# PCB-BI8-1x8SC3x.net
KiCad netlist of a schematic drawn in EAGLE
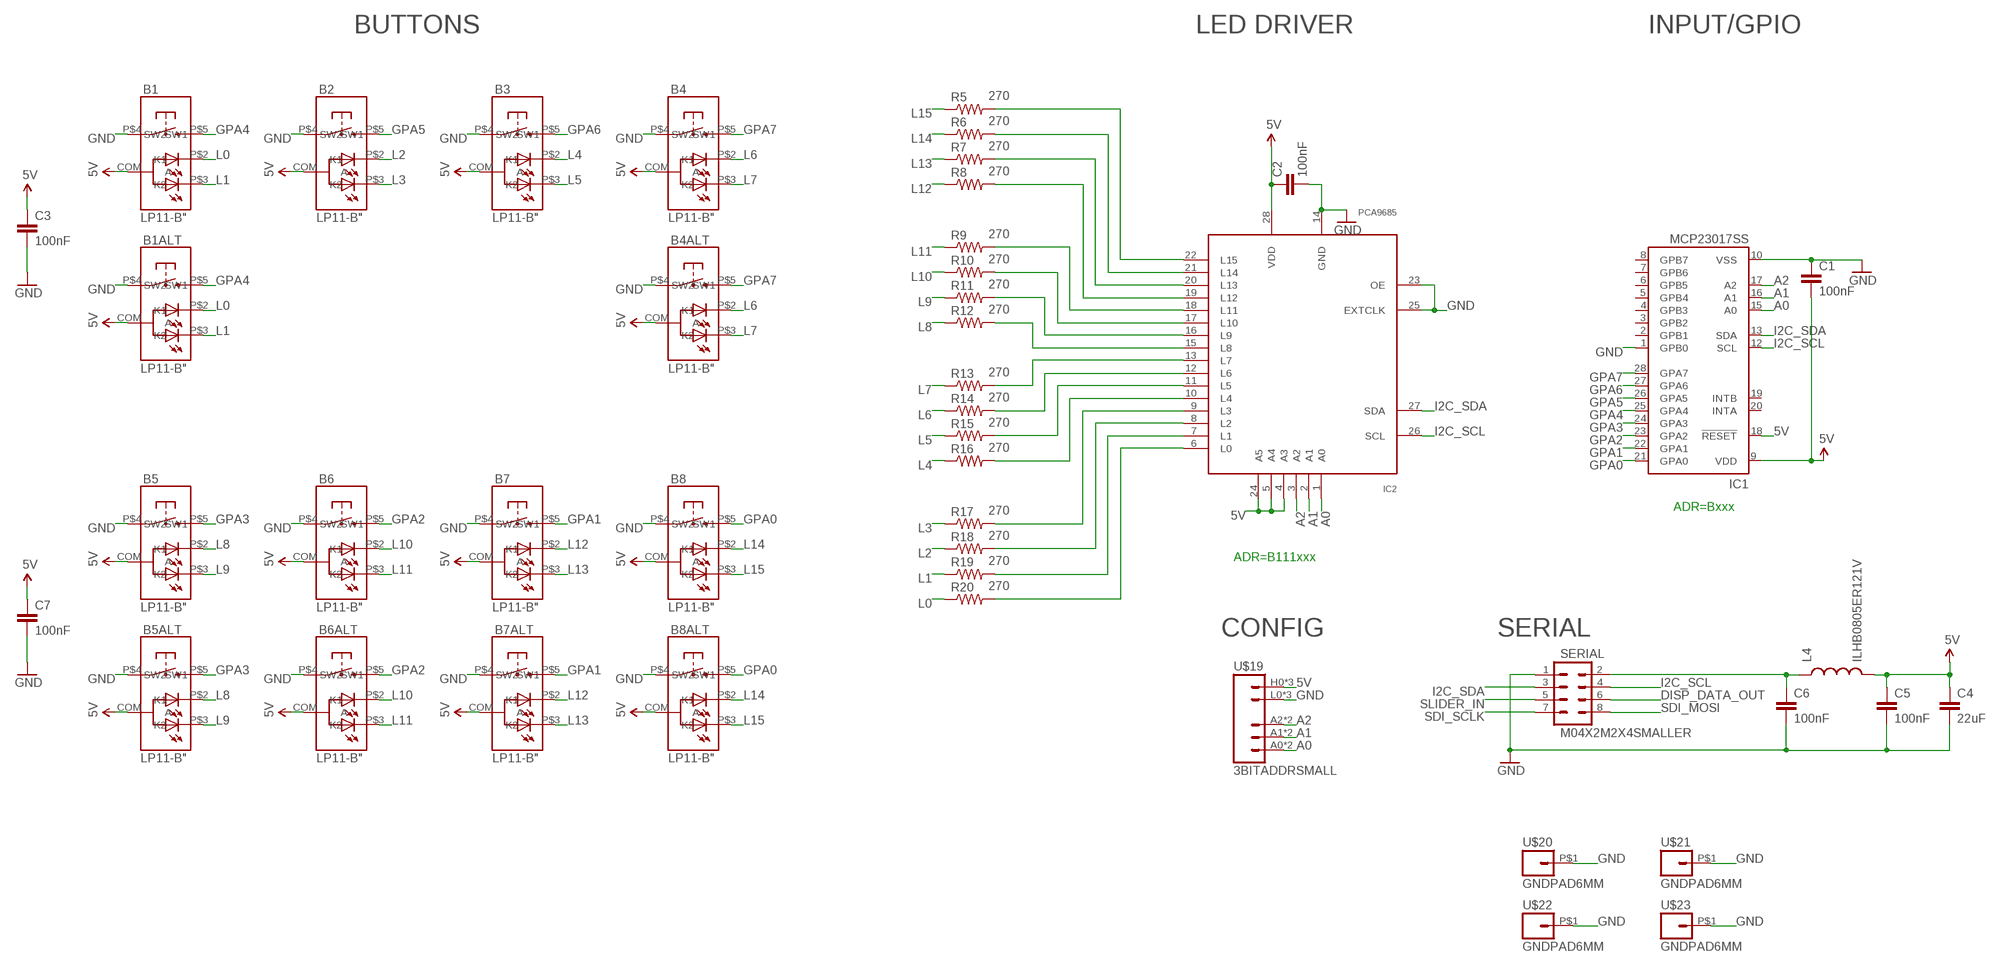
[diagram p0: schematic, sheet 1]

(export (version "E")
  (design (tool "Eeschema 10.0.6"))
  (components
    (comp (ref "B1")
      (value "LP11-B\"")
      (footprint "eagle-import:LP11")
      (libsource (lib "eagle-import") (part "LP11-B{dblquote}"))
    )
    (comp (ref "B1ALT")
      (value "LP11-B\"")
      (footprint "eagle-import:LP11")
      (libsource (lib "eagle-import") (part "LP11-B{dblquote}"))
    )
    (comp (ref "B2")
      (value "LP11-B\"")
      (footprint "eagle-import:LP11")
      (libsource (lib "eagle-import") (part "LP11-B{dblquote}"))
    )
    (comp (ref "B3")
      (value "LP11-B\"")
      (footprint "eagle-import:LP11")
      (libsource (lib "eagle-import") (part "LP11-B{dblquote}"))
    )
    (comp (ref "B4")
      (value "LP11-B\"")
      (footprint "eagle-import:LP11")
      (libsource (lib "eagle-import") (part "LP11-B{dblquote}"))
    )
    (comp (ref "B4ALT")
      (value "LP11-B\"")
      (footprint "eagle-import:LP11")
      (libsource (lib "eagle-import") (part "LP11-B{dblquote}"))
    )
    (comp (ref "B5")
      (value "LP11-B\"")
      (footprint "eagle-import:LP11")
      (libsource (lib "eagle-import") (part "LP11-B{dblquote}"))
    )
    (comp (ref "B5ALT")
      (value "LP11-B\"")
      (footprint "eagle-import:LP11")
      (libsource (lib "eagle-import") (part "LP11-B{dblquote}"))
    )
    (comp (ref "B6")
      (value "LP11-B\"")
      (footprint "eagle-import:LP11")
      (libsource (lib "eagle-import") (part "LP11-B{dblquote}"))
    )
    (comp (ref "B6ALT")
      (value "LP11-B\"")
      (footprint "eagle-import:LP11")
      (libsource (lib "eagle-import") (part "LP11-B{dblquote}"))
    )
    (comp (ref "B7")
      (value "LP11-B\"")
      (footprint "eagle-import:LP11")
      (libsource (lib "eagle-import") (part "LP11-B{dblquote}"))
    )
    (comp (ref "B7ALT")
      (value "LP11-B\"")
      (footprint "eagle-import:LP11")
      (libsource (lib "eagle-import") (part "LP11-B{dblquote}"))
    )
    (comp (ref "B8")
      (value "LP11-B\"")
      (footprint "eagle-import:LP11")
      (libsource (lib "eagle-import") (part "LP11-B{dblquote}"))
    )
    (comp (ref "B8ALT")
      (value "LP11-B\"")
      (footprint "eagle-import:LP11")
      (libsource (lib "eagle-import") (part "LP11-B{dblquote}"))
    )
    (comp (ref "C1")
      (value "100nF")
      (footprint "eagle-import:0603-CAP")
      (libsource (lib "eagle-import") (part "CAP0603-CAP"))
    )
    (comp (ref "C2")
      (value "100nF")
      (footprint "eagle-import:0603-CAP")
      (libsource (lib "eagle-import") (part "CAP0603-CAP"))
    )
    (comp (ref "C3")
      (value "100nF")
      (footprint "eagle-import:0603-CAP")
      (libsource (lib "eagle-import") (part "CAP0603-CAP"))
    )
    (comp (ref "C4")
      (value "22uF")
      (footprint "eagle-import:0805")
      (libsource (lib "eagle-import") (part "CAP0805"))
    )
    (comp (ref "C5")
      (value "100nF")
      (footprint "eagle-import:0603-CAP")
      (libsource (lib "eagle-import") (part "CAP0603-CAP"))
    )
    (comp (ref "C6")
      (value "100nF")
      (footprint "eagle-import:0603-CAP")
      (libsource (lib "eagle-import") (part "CAP0603-CAP"))
    )
    (comp (ref "C7")
      (value "100nF")
      (footprint "eagle-import:0603-CAP")
      (libsource (lib "eagle-import") (part "CAP0603-CAP"))
    )
    (comp (ref "IC1")
      (value "MCP23017SS")
      (footprint "eagle-import:SSOP28")
      (fields
        (field (name "MF") "MICROCHIP")
        (field (name "MPN") "MCP23017-E/SS")
        (field (name "MPN_1") "MCP23017-E/SS")
        (field (name "OC_FARNELL") "1467674")
        (field (name "OC_NEWARK") "31K2960")
      )
      (libsource (lib "eagle-import") (part "MCP23017SS"))
    )
    (comp (ref "IC2")
      (value "PCA9685")
      (footprint "eagle-import:TSSOP28")
      (libsource (lib "eagle-import") (part "PCA9685"))
    )
    (comp (ref "L4")
      (value "ILHB0805ER121V")
      (footprint "eagle-import:0805")
      (libsource (lib "eagle-import") (part "INDUCTOR0805"))
    )
    (comp (ref "R5")
      (value "270")
      (footprint "eagle-import:0603-RES")
      (libsource (lib "eagle-import") (part "RESISTOR0603-RES"))
    )
    (comp (ref "R6")
      (value "270")
      (footprint "eagle-import:0603-RES")
      (libsource (lib "eagle-import") (part "RESISTOR0603-RES"))
    )
    (comp (ref "R7")
      (value "270")
      (footprint "eagle-import:0603-RES")
      (libsource (lib "eagle-import") (part "RESISTOR0603-RES"))
    )
    (comp (ref "R8")
      (value "270")
      (footprint "eagle-import:0603-RES")
      (libsource (lib "eagle-import") (part "RESISTOR0603-RES"))
    )
    (comp (ref "R9")
      (value "270")
      (footprint "eagle-import:0603-RES")
      (libsource (lib "eagle-import") (part "RESISTOR0603-RES"))
    )
    (comp (ref "R10")
      (value "270")
      (footprint "eagle-import:0603-RES")
      (libsource (lib "eagle-import") (part "RESISTOR0603-RES"))
    )
    (comp (ref "R11")
      (value "270")
      (footprint "eagle-import:0603-RES")
      (libsource (lib "eagle-import") (part "RESISTOR0603-RES"))
    )
    (comp (ref "R12")
      (value "270")
      (footprint "eagle-import:0603-RES")
      (libsource (lib "eagle-import") (part "RESISTOR0603-RES"))
    )
    (comp (ref "R13")
      (value "270")
      (footprint "eagle-import:0603-RES")
      (libsource (lib "eagle-import") (part "RESISTOR0603-RES"))
    )
    (comp (ref "R14")
      (value "270")
      (footprint "eagle-import:0603-RES")
      (libsource (lib "eagle-import") (part "RESISTOR0603-RES"))
    )
    (comp (ref "R15")
      (value "270")
      (footprint "eagle-import:0603-RES")
      (libsource (lib "eagle-import") (part "RESISTOR0603-RES"))
    )
    (comp (ref "R16")
      (value "270")
      (footprint "eagle-import:0603-RES")
      (libsource (lib "eagle-import") (part "RESISTOR0603-RES"))
    )
    (comp (ref "R17")
      (value "270")
      (footprint "eagle-import:0603-RES")
      (libsource (lib "eagle-import") (part "RESISTOR0603-RES"))
    )
    (comp (ref "R18")
      (value "270")
      (footprint "eagle-import:0603-RES")
      (libsource (lib "eagle-import") (part "RESISTOR0603-RES"))
    )
    (comp (ref "R19")
      (value "270")
      (footprint "eagle-import:0603-RES")
      (libsource (lib "eagle-import") (part "RESISTOR0603-RES"))
    )
    (comp (ref "R20")
      (value "270")
      (footprint "eagle-import:0603-RES")
      (libsource (lib "eagle-import") (part "RESISTOR0603-RES"))
    )
    (comp (ref "SERIAL")
      (value "M04X2M2X4SMALLER")
      (footprint "eagle-import:M2X4SMALLER")
      (libsource (lib "eagle-import") (part "M04X2M2X4SMALLER"))
    )
    (comp (ref "U$19")
      (value "3BITADDRSMALL")
      (footprint "eagle-import:3BITADDR_SMALL")
      (libsource (lib "eagle-import") (part "3BITADDRSMALL"))
    )
    (comp (ref "U$20")
      (value "GNDPAD6MM")
      (footprint "eagle-import:3.2MMPAD6MM")
      (libsource (lib "eagle-import") (part "GNDPAD6MM"))
    )
    (comp (ref "U$21")
      (value "GNDPAD6MM")
      (footprint "eagle-import:3.2MMPAD6MM")
      (libsource (lib "eagle-import") (part "GNDPAD6MM"))
    )
    (comp (ref "U$22")
      (value "GNDPAD6MM")
      (footprint "eagle-import:3.2MMPAD6MM")
      (libsource (lib "eagle-import") (part "GNDPAD6MM"))
    )
    (comp (ref "U$23")
      (value "GNDPAD6MM")
      (footprint "eagle-import:3.2MMPAD6MM")
      (libsource (lib "eagle-import") (part "GNDPAD6MM"))
    )
  )
  (nets
    (net (code "1") (name "/A0") (class "Default")
      (node (ref "IC1") (pin "15") (pinfunction "A0_15") (pintype "input"))
      (node (ref "IC2") (pin "1") (pinfunction "A0_1") (pintype "input"))
      (node (ref "U$19") (pin "A0") (pinfunction "A0_A0") (pintype "passive"))
      (node (ref "U$19") (pin "AS0") (pinfunction "A0_AS0") (pintype "passive"))
    )
    (net (code "2") (name "/A1") (class "Default")
      (node (ref "IC1") (pin "16") (pinfunction "A1_16") (pintype "input"))
      (node (ref "IC2") (pin "2") (pinfunction "A1_2") (pintype "input"))
      (node (ref "U$19") (pin "A1") (pinfunction "A1_A1") (pintype "passive"))
      (node (ref "U$19") (pin "AS1") (pinfunction "A1_AS1") (pintype "passive"))
    )
    (net (code "3") (name "/A2") (class "Default")
      (node (ref "IC1") (pin "17") (pinfunction "A2_17") (pintype "input"))
      (node (ref "IC2") (pin "3") (pinfunction "A2_3") (pintype "input"))
      (node (ref "U$19") (pin "A2") (pinfunction "A2_A2") (pintype "passive"))
      (node (ref "U$19") (pin "AS2") (pinfunction "A2_AS2") (pintype "passive"))
    )
    (net (code "4") (name "/DISP_DATA_OUT") (class "Default")
      (node (ref "SERIAL") (pin "6") (pinfunction "6_6") (pintype "passive"))
    )
    (net (code "5") (name "/GPA0") (class "Default")
      (node (ref "B8") (pin "P$5") (pinfunction "SW2_P$5") (pintype "bidirectional"))
      (node (ref "B8ALT") (pin "P$5") (pinfunction "SW2_P$5") (pintype "bidirectional"))
      (node (ref "IC1") (pin "21") (pinfunction "GPA0_21") (pintype "bidirectional"))
    )
    (net (code "6") (name "/GPA1") (class "Default")
      (node (ref "B7") (pin "P$5") (pinfunction "SW2_P$5") (pintype "bidirectional"))
      (node (ref "B7ALT") (pin "P$5") (pinfunction "SW2_P$5") (pintype "bidirectional"))
      (node (ref "IC1") (pin "22") (pinfunction "GPA1_22") (pintype "bidirectional"))
    )
    (net (code "7") (name "/GPA2") (class "Default")
      (node (ref "B6") (pin "P$5") (pinfunction "SW2_P$5") (pintype "bidirectional"))
      (node (ref "B6ALT") (pin "P$5") (pinfunction "SW2_P$5") (pintype "bidirectional"))
      (node (ref "IC1") (pin "23") (pinfunction "GPA2_23") (pintype "bidirectional"))
    )
    (net (code "8") (name "/GPA3") (class "Default")
      (node (ref "B5") (pin "P$5") (pinfunction "SW2_P$5") (pintype "bidirectional"))
      (node (ref "B5ALT") (pin "P$5") (pinfunction "SW2_P$5") (pintype "bidirectional"))
      (node (ref "IC1") (pin "24") (pinfunction "GPA3_24") (pintype "bidirectional"))
    )
    (net (code "9") (name "/GPA4") (class "Default")
      (node (ref "B1") (pin "P$5") (pinfunction "SW2_P$5") (pintype "bidirectional"))
      (node (ref "B1ALT") (pin "P$5") (pinfunction "SW2_P$5") (pintype "bidirectional"))
      (node (ref "IC1") (pin "25") (pinfunction "GPA4_25") (pintype "bidirectional"))
    )
    (net (code "10") (name "/GPA5") (class "Default")
      (node (ref "B2") (pin "P$5") (pinfunction "SW2_P$5") (pintype "bidirectional"))
      (node (ref "IC1") (pin "26") (pinfunction "GPA5_26") (pintype "bidirectional"))
    )
    (net (code "11") (name "/GPA6") (class "Default")
      (node (ref "B3") (pin "P$5") (pinfunction "SW2_P$5") (pintype "bidirectional"))
      (node (ref "IC1") (pin "27") (pinfunction "GPA6_27") (pintype "bidirectional"))
    )
    (net (code "12") (name "/GPA7") (class "Default")
      (node (ref "B4") (pin "P$5") (pinfunction "SW2_P$5") (pintype "bidirectional"))
      (node (ref "B4ALT") (pin "P$5") (pinfunction "SW2_P$5") (pintype "bidirectional"))
      (node (ref "IC1") (pin "28") (pinfunction "GPA7_28") (pintype "bidirectional"))
    )
    (net (code "13") (name "/I2C_SCL") (class "Default")
      (node (ref "IC1") (pin "12") (pinfunction "SCL_12") (pintype "input"))
      (node (ref "IC2") (pin "26") (pinfunction "SCL_26") (pintype "input"))
      (node (ref "SERIAL") (pin "4") (pinfunction "4_4") (pintype "passive"))
    )
    (net (code "14") (name "/I2C_SDA") (class "Default")
      (node (ref "IC1") (pin "13") (pinfunction "SDA_13") (pintype "bidirectional"))
      (node (ref "IC2") (pin "27") (pinfunction "SDA_27") (pintype "input"))
      (node (ref "SERIAL") (pin "3") (pinfunction "3_3") (pintype "passive"))
    )
    (net (code "15") (name "/L0") (class "Default")
      (node (ref "B1") (pin "P$2") (pinfunction "K1_P$2") (pintype "bidirectional"))
      (node (ref "B1ALT") (pin "P$2") (pinfunction "K1_P$2") (pintype "bidirectional"))
      (node (ref "R20") (pin "1") (pinfunction "1_1") (pintype "passive"))
    )
    (net (code "16") (name "/L1") (class "Default")
      (node (ref "B1") (pin "P$3") (pinfunction "K2_P$3") (pintype "bidirectional"))
      (node (ref "B1ALT") (pin "P$3") (pinfunction "K2_P$3") (pintype "bidirectional"))
      (node (ref "R19") (pin "1") (pinfunction "1_1") (pintype "passive"))
    )
    (net (code "17") (name "/L2") (class "Default")
      (node (ref "B2") (pin "P$2") (pinfunction "K1_P$2") (pintype "bidirectional"))
      (node (ref "R18") (pin "1") (pinfunction "1_1") (pintype "passive"))
    )
    (net (code "18") (name "/L3") (class "Default")
      (node (ref "B2") (pin "P$3") (pinfunction "K2_P$3") (pintype "bidirectional"))
      (node (ref "R17") (pin "1") (pinfunction "1_1") (pintype "passive"))
    )
    (net (code "19") (name "/L4") (class "Default")
      (node (ref "B3") (pin "P$2") (pinfunction "K1_P$2") (pintype "bidirectional"))
      (node (ref "R16") (pin "1") (pinfunction "1_1") (pintype "passive"))
    )
    (net (code "20") (name "/L5") (class "Default")
      (node (ref "B3") (pin "P$3") (pinfunction "K2_P$3") (pintype "bidirectional"))
      (node (ref "R15") (pin "1") (pinfunction "1_1") (pintype "passive"))
    )
    (net (code "21") (name "/L6") (class "Default")
      (node (ref "B4") (pin "P$2") (pinfunction "K1_P$2") (pintype "bidirectional"))
      (node (ref "B4ALT") (pin "P$2") (pinfunction "K1_P$2") (pintype "bidirectional"))
      (node (ref "R14") (pin "1") (pinfunction "1_1") (pintype "passive"))
    )
    (net (code "22") (name "/L7") (class "Default")
      (node (ref "B4") (pin "P$3") (pinfunction "K2_P$3") (pintype "bidirectional"))
      (node (ref "B4ALT") (pin "P$3") (pinfunction "K2_P$3") (pintype "bidirectional"))
      (node (ref "R13") (pin "1") (pinfunction "1_1") (pintype "passive"))
    )
    (net (code "23") (name "/L8") (class "Default")
      (node (ref "B5") (pin "P$2") (pinfunction "K1_P$2") (pintype "bidirectional"))
      (node (ref "B5ALT") (pin "P$2") (pinfunction "K1_P$2") (pintype "bidirectional"))
      (node (ref "R12") (pin "1") (pinfunction "1_1") (pintype "passive"))
    )
    (net (code "24") (name "/L9") (class "Default")
      (node (ref "B5") (pin "P$3") (pinfunction "K2_P$3") (pintype "bidirectional"))
      (node (ref "B5ALT") (pin "P$3") (pinfunction "K2_P$3") (pintype "bidirectional"))
      (node (ref "R11") (pin "1") (pinfunction "1_1") (pintype "passive"))
    )
    (net (code "25") (name "/L10") (class "Default")
      (node (ref "B6") (pin "P$2") (pinfunction "K1_P$2") (pintype "bidirectional"))
      (node (ref "B6ALT") (pin "P$2") (pinfunction "K1_P$2") (pintype "bidirectional"))
      (node (ref "R10") (pin "1") (pinfunction "1_1") (pintype "passive"))
    )
    (net (code "26") (name "/L11") (class "Default")
      (node (ref "B6") (pin "P$3") (pinfunction "K2_P$3") (pintype "bidirectional"))
      (node (ref "B6ALT") (pin "P$3") (pinfunction "K2_P$3") (pintype "bidirectional"))
      (node (ref "R9") (pin "1") (pinfunction "1_1") (pintype "passive"))
    )
    (net (code "27") (name "/L12") (class "Default")
      (node (ref "B7") (pin "P$2") (pinfunction "K1_P$2") (pintype "bidirectional"))
      (node (ref "B7ALT") (pin "P$2") (pinfunction "K1_P$2") (pintype "bidirectional"))
      (node (ref "R8") (pin "1") (pinfunction "1_1") (pintype "passive"))
    )
    (net (code "28") (name "/L13") (class "Default")
      (node (ref "B7") (pin "P$3") (pinfunction "K2_P$3") (pintype "bidirectional"))
      (node (ref "B7ALT") (pin "P$3") (pinfunction "K2_P$3") (pintype "bidirectional"))
      (node (ref "R7") (pin "1") (pinfunction "1_1") (pintype "passive"))
    )
    (net (code "29") (name "/L14") (class "Default")
      (node (ref "B8") (pin "P$2") (pinfunction "K1_P$2") (pintype "bidirectional"))
      (node (ref "B8ALT") (pin "P$2") (pinfunction "K1_P$2") (pintype "bidirectional"))
      (node (ref "R6") (pin "1") (pinfunction "1_1") (pintype "passive"))
    )
    (net (code "30") (name "/L15") (class "Default")
      (node (ref "B8") (pin "P$3") (pinfunction "K2_P$3") (pintype "bidirectional"))
      (node (ref "B8ALT") (pin "P$3") (pinfunction "K2_P$3") (pintype "bidirectional"))
      (node (ref "R5") (pin "1") (pinfunction "1_1") (pintype "passive"))
    )
    (net (code "31") (name "/SDI_MOSI") (class "Default")
      (node (ref "SERIAL") (pin "8") (pinfunction "8_8") (pintype "passive"))
    )
    (net (code "32") (name "/SDI_SCLK") (class "Default")
      (node (ref "SERIAL") (pin "7") (pinfunction "7_7") (pintype "passive"))
    )
    (net (code "33") (name "/SLIDER_IN") (class "Default")
      (node (ref "SERIAL") (pin "5") (pinfunction "5_5") (pintype "passive"))
    )
    (net (code "34") (name "5V") (class "Default")
      (node (ref "B1") (pin "COM") (pinfunction "A_COM") (pintype "bidirectional"))
      (node (ref "B1ALT") (pin "COM") (pinfunction "A_COM") (pintype "bidirectional"))
      (node (ref "B2") (pin "COM") (pinfunction "A_COM") (pintype "bidirectional"))
      (node (ref "B3") (pin "COM") (pinfunction "A_COM") (pintype "bidirectional"))
      (node (ref "B4") (pin "COM") (pinfunction "A_COM") (pintype "bidirectional"))
      (node (ref "B4ALT") (pin "COM") (pinfunction "A_COM") (pintype "bidirectional"))
      (node (ref "B5") (pin "COM") (pinfunction "A_COM") (pintype "bidirectional"))
      (node (ref "B5ALT") (pin "COM") (pinfunction "A_COM") (pintype "bidirectional"))
      (node (ref "B6") (pin "COM") (pinfunction "A_COM") (pintype "bidirectional"))
      (node (ref "B6ALT") (pin "COM") (pinfunction "A_COM") (pintype "bidirectional"))
      (node (ref "B7") (pin "COM") (pinfunction "A_COM") (pintype "bidirectional"))
      (node (ref "B7ALT") (pin "COM") (pinfunction "A_COM") (pintype "bidirectional"))
      (node (ref "B8") (pin "COM") (pinfunction "A_COM") (pintype "bidirectional"))
      (node (ref "B8ALT") (pin "COM") (pinfunction "A_COM") (pintype "bidirectional"))
      (node (ref "C1") (pin "2") (pinfunction "2_2") (pintype "passive"))
      (node (ref "C2") (pin "1") (pinfunction "1_1") (pintype "passive"))
      (node (ref "C3") (pin "1") (pinfunction "1_1") (pintype "passive"))
      (node (ref "C4") (pin "1") (pinfunction "1_1") (pintype "passive"))
      (node (ref "C5") (pin "1") (pinfunction "1_1") (pintype "passive"))
      (node (ref "C7") (pin "1") (pinfunction "1_1") (pintype "passive"))
      (node (ref "IC1") (pin "18") (pinfunction "~{RESET}_18") (pintype "input"))
      (node (ref "IC1") (pin "9") (pinfunction "VDD_9") (pintype "power_in"))
      (node (ref "IC2") (pin "24") (pinfunction "A5_24") (pintype "input"))
      (node (ref "IC2") (pin "28") (pinfunction "VDD_28") (pintype "power_in"))
      (node (ref "IC2") (pin "4") (pinfunction "A3_4") (pintype "input"))
      (node (ref "IC2") (pin "5") (pinfunction "A4_5") (pintype "input"))
      (node (ref "L4") (pin "2") (pinfunction "2_2") (pintype "passive"))
      (node (ref "U$19") (pin "H0") (pinfunction "VCC_H0") (pintype "passive"))
      (node (ref "U$19") (pin "H1") (pinfunction "VCC_H1") (pintype "passive"))
      (node (ref "U$19") (pin "H2") (pinfunction "VCC_H2") (pintype "passive"))
    )
    (net (code "35") (name "GND") (class "Default")
      (node (ref "B1") (pin "P$4") (pinfunction "SW1_P$4") (pintype "bidirectional"))
      (node (ref "B1ALT") (pin "P$4") (pinfunction "SW1_P$4") (pintype "bidirectional"))
      (node (ref "B2") (pin "P$4") (pinfunction "SW1_P$4") (pintype "bidirectional"))
      (node (ref "B3") (pin "P$4") (pinfunction "SW1_P$4") (pintype "bidirectional"))
      (node (ref "B4") (pin "P$4") (pinfunction "SW1_P$4") (pintype "bidirectional"))
      (node (ref "B4ALT") (pin "P$4") (pinfunction "SW1_P$4") (pintype "bidirectional"))
      (node (ref "B5") (pin "P$4") (pinfunction "SW1_P$4") (pintype "bidirectional"))
      (node (ref "B5ALT") (pin "P$4") (pinfunction "SW1_P$4") (pintype "bidirectional"))
      (node (ref "B6") (pin "P$4") (pinfunction "SW1_P$4") (pintype "bidirectional"))
      (node (ref "B6ALT") (pin "P$4") (pinfunction "SW1_P$4") (pintype "bidirectional"))
      (node (ref "B7") (pin "P$4") (pinfunction "SW1_P$4") (pintype "bidirectional"))
      (node (ref "B7ALT") (pin "P$4") (pinfunction "SW1_P$4") (pintype "bidirectional"))
      (node (ref "B8") (pin "P$4") (pinfunction "SW1_P$4") (pintype "bidirectional"))
      (node (ref "B8ALT") (pin "P$4") (pinfunction "SW1_P$4") (pintype "bidirectional"))
      (node (ref "C1") (pin "1") (pinfunction "1_1") (pintype "passive"))
      (node (ref "C2") (pin "2") (pinfunction "2_2") (pintype "passive"))
      (node (ref "C3") (pin "2") (pinfunction "2_2") (pintype "passive"))
      (node (ref "C4") (pin "2") (pinfunction "2_2") (pintype "passive"))
      (node (ref "C5") (pin "2") (pinfunction "2_2") (pintype "passive"))
      (node (ref "C6") (pin "2") (pinfunction "2_2") (pintype "passive"))
      (node (ref "C7") (pin "2") (pinfunction "2_2") (pintype "passive"))
      (node (ref "IC1") (pin "1") (pinfunction "GPB0_1") (pintype "bidirectional"))
      (node (ref "IC1") (pin "10") (pinfunction "VSS_10") (pintype "power_in"))
      (node (ref "IC2") (pin "14") (pinfunction "GND_14") (pintype "power_in"))
      (node (ref "IC2") (pin "23") (pinfunction "OE_23") (pintype "input"))
      (node (ref "IC2") (pin "25") (pinfunction "EXTCLK_25") (pintype "input"))
      (node (ref "SERIAL") (pin "1") (pinfunction "1_1") (pintype "passive"))
      (node (ref "U$19") (pin "L0") (pinfunction "GND_L0") (pintype "passive"))
      (node (ref "U$19") (pin "L1") (pinfunction "GND_L1") (pintype "passive"))
      (node (ref "U$19") (pin "L2") (pinfunction "GND_L2") (pintype "passive"))
      (node (ref "U$20") (pin "P$1") (pinfunction "1_P$1") (pintype "passive"))
      (node (ref "U$21") (pin "P$1") (pinfunction "1_P$1") (pintype "passive"))
      (node (ref "U$22") (pin "P$1") (pinfunction "1_P$1") (pintype "passive"))
      (node (ref "U$23") (pin "P$1") (pinfunction "1_P$1") (pintype "passive"))
    )
    (net (code "36") (name "Net-(C6-Pad1)") (class "Default")
      (node (ref "C6") (pin "1") (pinfunction "1_1") (pintype "passive"))
      (node (ref "L4") (pin "1") (pinfunction "1_1") (pintype "passive"))
      (node (ref "SERIAL") (pin "2") (pinfunction "2_2") (pintype "passive"))
    )
    (net (code "37") (name "Net-(IC2-L0)") (class "Default")
      (node (ref "IC2") (pin "6") (pinfunction "L0_6") (pintype "output"))
      (node (ref "R20") (pin "2") (pinfunction "2_2") (pintype "passive"))
    )
    (net (code "38") (name "Net-(IC2-L1)") (class "Default")
      (node (ref "IC2") (pin "7") (pinfunction "L1_7") (pintype "output"))
      (node (ref "R19") (pin "2") (pinfunction "2_2") (pintype "passive"))
    )
    (net (code "39") (name "Net-(IC2-L2)") (class "Default")
      (node (ref "IC2") (pin "8") (pinfunction "L2_8") (pintype "output"))
      (node (ref "R18") (pin "2") (pinfunction "2_2") (pintype "passive"))
    )
    (net (code "40") (name "Net-(IC2-L3)") (class "Default")
      (node (ref "IC2") (pin "9") (pinfunction "L3_9") (pintype "output"))
      (node (ref "R17") (pin "2") (pinfunction "2_2") (pintype "passive"))
    )
    (net (code "41") (name "Net-(IC2-L4)") (class "Default")
      (node (ref "IC2") (pin "10") (pinfunction "L4_10") (pintype "output"))
      (node (ref "R16") (pin "2") (pinfunction "2_2") (pintype "passive"))
    )
    (net (code "42") (name "Net-(IC2-L5)") (class "Default")
      (node (ref "IC2") (pin "11") (pinfunction "L5_11") (pintype "output"))
      (node (ref "R15") (pin "2") (pinfunction "2_2") (pintype "passive"))
    )
    (net (code "43") (name "Net-(IC2-L6)") (class "Default")
      (node (ref "IC2") (pin "12") (pinfunction "L6_12") (pintype "output"))
      (node (ref "R14") (pin "2") (pinfunction "2_2") (pintype "passive"))
    )
    (net (code "44") (name "Net-(IC2-L7)") (class "Default")
      (node (ref "IC2") (pin "13") (pinfunction "L7_13") (pintype "output"))
      (node (ref "R13") (pin "2") (pinfunction "2_2") (pintype "passive"))
    )
    (net (code "45") (name "Net-(IC2-L8)") (class "Default")
      (node (ref "IC2") (pin "15") (pinfunction "L8_15") (pintype "output"))
      (node (ref "R12") (pin "2") (pinfunction "2_2") (pintype "passive"))
    )
    (net (code "46") (name "Net-(IC2-L9)") (class "Default")
      (node (ref "IC2") (pin "16") (pinfunction "L9_16") (pintype "output"))
      (node (ref "R11") (pin "2") (pinfunction "2_2") (pintype "passive"))
    )
    (net (code "47") (name "Net-(IC2-L10)") (class "Default")
      (node (ref "IC2") (pin "17") (pinfunction "L10_17") (pintype "output"))
      (node (ref "R10") (pin "2") (pinfunction "2_2") (pintype "passive"))
    )
    (net (code "48") (name "Net-(IC2-L11)") (class "Default")
      (node (ref "IC2") (pin "18") (pinfunction "L11_18") (pintype "output"))
      (node (ref "R9") (pin "2") (pinfunction "2_2") (pintype "passive"))
    )
    (net (code "49") (name "Net-(IC2-L12)") (class "Default")
      (node (ref "IC2") (pin "19") (pinfunction "L12_19") (pintype "output"))
      (node (ref "R8") (pin "2") (pinfunction "2_2") (pintype "passive"))
    )
    (net (code "50") (name "Net-(IC2-L13)") (class "Default")
      (node (ref "IC2") (pin "20") (pinfunction "L13_20") (pintype "output"))
      (node (ref "R7") (pin "2") (pinfunction "2_2") (pintype "passive"))
    )
    (net (code "51") (name "Net-(IC2-L14)") (class "Default")
      (node (ref "IC2") (pin "21") (pinfunction "L14_21") (pintype "output"))
      (node (ref "R6") (pin "2") (pinfunction "2_2") (pintype "passive"))
    )
    (net (code "52") (name "Net-(IC2-L15)") (class "Default")
      (node (ref "IC2") (pin "22") (pinfunction "L15_22") (pintype "output"))
      (node (ref "R5") (pin "2") (pinfunction "2_2") (pintype "passive"))
    )
    (net (code "53") (name "unconnected-(IC1-GPB1-Pad2)") (class "Default")
      (node (ref "IC1") (pin "2") (pinfunction "GPB1_2") (pintype "bidirectional"))
    )
    (net (code "54") (name "unconnected-(IC1-GPB2-Pad3)") (class "Default")
      (node (ref "IC1") (pin "3") (pinfunction "GPB2_3") (pintype "bidirectional"))
    )
    (net (code "55") (name "unconnected-(IC1-GPB3-Pad4)") (class "Default")
      (node (ref "IC1") (pin "4") (pinfunction "GPB3_4") (pintype "bidirectional"))
    )
    (net (code "56") (name "unconnected-(IC1-GPB4-Pad5)") (class "Default")
      (node (ref "IC1") (pin "5") (pinfunction "GPB4_5") (pintype "bidirectional"))
    )
    (net (code "57") (name "unconnected-(IC1-GPB5-Pad6)") (class "Default")
      (node (ref "IC1") (pin "6") (pinfunction "GPB5_6") (pintype "bidirectional"))
    )
    (net (code "58") (name "unconnected-(IC1-GPB6-Pad7)") (class "Default")
      (node (ref "IC1") (pin "7") (pinfunction "GPB6_7") (pintype "bidirectional"))
    )
    (net (code "59") (name "unconnected-(IC1-GPB7-Pad8)") (class "Default")
      (node (ref "IC1") (pin "8") (pinfunction "GPB7_8") (pintype "bidirectional"))
    )
    (net (code "60") (name "unconnected-(IC1-INTA-Pad20)") (class "Default")
      (node (ref "IC1") (pin "20") (pinfunction "INTA_20") (pintype "output"))
    )
    (net (code "61") (name "unconnected-(IC1-INTB-Pad19)") (class "Default")
      (node (ref "IC1") (pin "19") (pinfunction "INTB_19") (pintype "output"))
    )
  )
)
